# Sheet4.net
KiCad netlist of a schematic drawn in Altium Designer
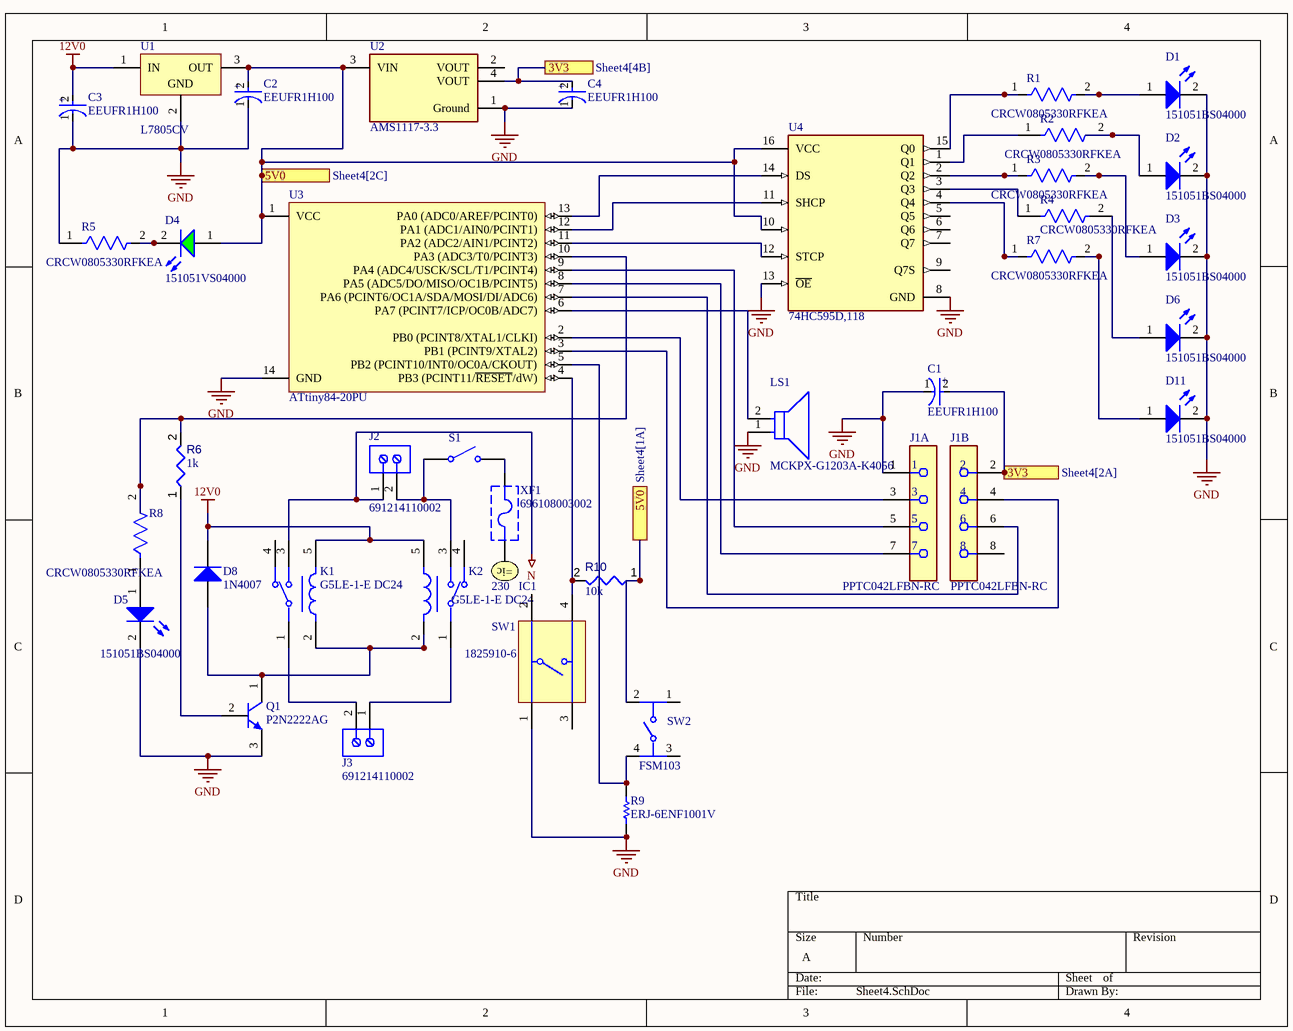
[diagram p0: Sheet4.SchDoc]

(export (version "E")
  (design (tool "Eeschema 10.0.6"))
  (components
    (comp (ref "C1")
      (value "EEUFR1H100")
      (footprint "FP-RAD-TH-D_5_0_5-L_11_1-MFG")
      (description "Aluminum Electrolytic Capacitors (Radial Lead Type) 10uF ±20% 50V")
      (fields (field (name "TOLERANCE") "20%") (field (name "VOLTAGE") "50V"))
      (libsource (lib "Altium Content Vault") (part "a00bbbee19879c290e62620ae7e47b1"))
    )
    (comp (ref "C2")
      (value "EEUFR1H100")
      (footprint "FP-RAD-TH-D_5_0_5-L_11_1-MFG")
      (description "Aluminum Electrolytic Capacitors (Radial Lead Type) 10uF ±20% 50V")
      (fields (field (name "TOLERANCE") "20%") (field (name "VOLTAGE") "50V"))
      (libsource (lib "Altium Content Vault") (part "a00bbbee19879c290e62620ae7e47b1"))
    )
    (comp (ref "C3")
      (value "EEUFR1H100")
      (footprint "FP-RAD-TH-D_5_0_5-L_11_1-MFG")
      (description "Aluminum Electrolytic Capacitors (Radial Lead Type) 10uF ±20% 50V")
      (fields (field (name "TOLERANCE") "20%") (field (name "VOLTAGE") "50V"))
      (libsource (lib "Altium Content Vault") (part "a00bbbee19879c290e62620ae7e47b1"))
    )
    (comp (ref "C4")
      (value "EEUFR1H100")
      (footprint "FP-RAD-TH-D_5_0_5-L_11_1-MFG")
      (description "Aluminum Electrolytic Capacitors (Radial Lead Type) 10uF ±20% 50V")
      (fields (field (name "TOLERANCE") "20%") (field (name "VOLTAGE") "50V"))
      (libsource (lib "Altium Content Vault") (part "a00bbbee19879c290e62620ae7e47b1"))
    )
    (comp (ref "D1")
      (value "151051BS04000")
      (footprint "WL-TMRC_D5.9H8.7")
      (libsource (lib "Altium Content Vault") (part "LED_Blue_1A-2K"))
    )
    (comp (ref "D2")
      (value "151051BS04000")
      (footprint "WL-TMRC_D5.9H8.7")
      (libsource (lib "Altium Content Vault") (part "LED_Blue_1A-2K"))
    )
    (comp (ref "D3")
      (value "151051BS04000")
      (footprint "WL-TMRC_D5.9H8.7")
      (libsource (lib "Altium Content Vault") (part "LED_Blue_1A-2K"))
    )
    (comp (ref "D4")
      (value "151051VS04000")
      (footprint "WL-TMRC_D5.9H8.7")
      (libsource (lib "Altium Content Vault") (part "LED_Green_1A-2K"))
    )
    (comp (ref "D5")
      (value "151051BS04000")
      (footprint "WL-TMRC_D5.9H8.7")
      (libsource (lib "Altium Content Vault") (part "LED_Blue_1A-2K"))
    )
    (comp (ref "D6")
      (value "151051BS04000")
      (footprint "WL-TMRC_D5.9H8.7")
      (libsource (lib "Altium Content Vault") (part "LED_Blue_1A-2K"))
    )
    (comp (ref "D8")
      (value "1N4007")
      (footprint "FAIR-DO-41-2")
      (description "General Purpose Rectifier, 1.1 V, 1.0 A, -55 to 175 degC, 2-Pin DO-41, RoHS, Tape and Reel")
      (fields (field (name "MANUFACTURER") "Fairchild"))
      (libsource (lib "Adheesha") (part "KESE-D_K1A2-2"))
    )
    (comp (ref "D11")
      (value "151051BS04000")
      (footprint "WL-TMRC_D5.9H8.7")
      (libsource (lib "Altium Content Vault") (part "LED_Blue_1A-2K"))
    )
    (comp (ref "IC1")
      (value "Initial Condition")
      (fields (field (name "INITIAL VOLTAGE") "230"))
      (libsource (lib "Simulation Generic Components") (part ".IC"))
    )
    (comp (ref "J1")
      (value "PPTC042LFBN-RC")
      (footprint "FP-PPTC042LFBN-RC-MFG")
      (description "CONN HDR 8POS 0.1 TIN PCB")
      (fields
        (field (name "OCTOPART") "https://octopart.com/pptc042lfbn-rc-sullins-271088")
        (field (name "MANUFACTURER") "Sullins")
      )
      (libsource (lib "") (part "f7953d7cc9e5fc6ef8e06ef09a26288_1"))
    )
    (comp (ref "J2")
      (value "691214110002")
      (footprint "691214110002")
      (fields (field (name "VOLTAGE") "300V"))
      (libsource (lib "Altium Content Vault") (part "TBL - 1R - 02P - Screw"))
    )
    (comp (ref "J3")
      (value "691214110002")
      (footprint "691214110002")
      (fields (field (name "VOLTAGE") "300V"))
      (libsource (lib "Altium Content Vault") (part "TBL - 1R - 02P - Screw"))
    )
    (comp (ref "K1")
      (value "G5LE-1-E DC24")
      (footprint "FP-G5LE-1-E_DC24-MFG")
      (description "RELAY GEN PURPOSE SPDT 16A 24V")
      (libsource (lib "Altium Content Vault") (part "c03b8d08e5d02e70a6880f365e34168"))
    )
    (comp (ref "K2")
      (value "G5LE-1-E DC24")
      (footprint "FP-G5LE-1-E_DC24-MFG")
      (description "RELAY GEN PURPOSE SPDT 16A 24V")
      (libsource (lib "") (part "c03b8d08e5d02e70a6880f365e34168_1"))
    )
    (comp (ref "LS1")
      (value "MCKPX-G1203A-K4056")
      (footprint "FP-MCKPX-G1203A-K4056-MFG")
      (description "MAGNETIC BUZZER AND TRANSDUCER - More Details")
      (fields
        (field (name "MANUFACTURER") "Multicomp Pro")
        (field (name "OCTOPART") "https://octopart.com/mckpx-g1203a-k4056-multicomp-12157154")
      )
      (libsource (lib "Altium Content Vault") (part "1973c4b650225fd2ddacaff6b763965"))
    )
    (comp (ref "Q1")
      (value "P2N2222AG")
      (footprint "ONSC-TO-92-3-29-11")
      (description "Amplifier Transistor, NPN Silicon, 3-Pin TO-92, Pb-Free, Bulk Box")
      (fields (field (name "MANUFACTURER") "On Semiconductor"))
      (libsource (lib "Altium Content Vault") (part "ONSC-NPN-C1B2E3-3"))
    )
    (comp (ref "R1")
      (value "CRCW0805330RFKEA")
      (footprint "FP-CRCW0805-e3-MFG")
      (description "RES Thick Film, 330Ω, 1%, 0.125W, 100ppm/°C, 0805")
      (fields (field (name "TOLERANCE") "1%"))
      (libsource (lib "Altium Content Vault") (part "1029c3af85768c4190bb7ad29bc67b5"))
    )
    (comp (ref "R2")
      (value "CRCW0805330RFKEA")
      (footprint "FP-CRCW0805-e3-MFG")
      (description "RES Thick Film, 330Ω, 1%, 0.125W, 100ppm/°C, 0805")
      (fields (field (name "TOLERANCE") "1%"))
      (libsource (lib "Altium Content Vault") (part "1029c3af85768c4190bb7ad29bc67b5"))
    )
    (comp (ref "R3")
      (value "CRCW0805330RFKEA")
      (footprint "FP-CRCW0805-e3-MFG")
      (description "RES Thick Film, 330Ω, 1%, 0.125W, 100ppm/°C, 0805")
      (fields (field (name "TOLERANCE") "1%"))
      (libsource (lib "Altium Content Vault") (part "1029c3af85768c4190bb7ad29bc67b5"))
    )
    (comp (ref "R4")
      (value "CRCW0805330RFKEA")
      (footprint "FP-CRCW0805-e3-MFG")
      (description "RES Thick Film, 330Ω, 1%, 0.125W, 100ppm/°C, 0805")
      (fields (field (name "TOLERANCE") "1%"))
      (libsource (lib "Altium Content Vault") (part "1029c3af85768c4190bb7ad29bc67b5"))
    )
    (comp (ref "R5")
      (value "CRCW0805330RFKEA")
      (footprint "FP-CRCW0805-e3-MFG")
      (description "RES Thick Film, 330Ω, 1%, 0.125W, 100ppm/°C, 0805")
      (fields (field (name "TOLERANCE") "1%"))
      (libsource (lib "Altium Content Vault") (part "1029c3af85768c4190bb7ad29bc67b5"))
    )
    (comp (ref "R6")
      (value "1k")
      (footprint "RESA60-630X240")
      (description "Axial Resistor, 47.5 KOhm, +/- 1%, 0.25 W, -55 to 155 degC, 2-Pin THD, RoHS, Bulk")
      (fields (field (name "MANUFACTURER") "Yageo") (field (name "TOLERANCE") "1%"))
      (libsource (lib "Adheesha") (part "RES-2"))
    )
    (comp (ref "R7")
      (value "CRCW0805330RFKEA")
      (footprint "FP-CRCW0805-e3-MFG")
      (description "RES Thick Film, 330Ω, 1%, 0.125W, 100ppm/°C, 0805")
      (fields (field (name "TOLERANCE") "1%"))
      (libsource (lib "Altium Content Vault") (part "1029c3af85768c4190bb7ad29bc67b5"))
    )
    (comp (ref "R8")
      (value "CRCW0805330RFKEA")
      (footprint "FP-CRCW0805-e3-MFG")
      (description "RES Thick Film, 330Ω, 1%, 0.125W, 100ppm/°C, 0805")
      (fields (field (name "TOLERANCE") "1%"))
      (libsource (lib "Altium Content Vault") (part "1029c3af85768c4190bb7ad29bc67b5"))
    )
    (comp (ref "R9")
      (value "ERJ-6ENF1001V")
      (footprint "RESC2013X70X40ML20T20")
      (description "Chip Resistor, 1 KOhm, +/- 1%, 0.125 W, -55 to 155 degC, 0805 (2012 Metric), RoHS, Tape and Reel")
      (fields (field (name "MANUFACTURER") "Panasonic"))
      (libsource (lib "Altium Content Vault") (part "RES-2"))
    )
    (comp (ref "R10")
      (value "10k")
      (footprint "RESA60-630X240")
      (description "Axial Resistor, 47.5 KOhm, +/- 1%, 0.25 W, -55 to 155 degC, 2-Pin THD, RoHS, Bulk")
      (fields (field (name "MANUFACTURER") "Yageo") (field (name "TOLERANCE") "1%"))
      (libsource (lib "Adheesha") (part "RES-2"))
    )
    (comp (ref "S1")
      (value "Single-Pole, Single-Throw Switch")
      (libsource (lib "Simulation Generic Components") (part "SPST SW"))
    )
    (comp (ref "SW1")
      (value "1825910-6")
      (footprint "TECO-1825910-6_V")
      (description "Tact Switch, SPST-NO, 0.05 A, -35 to 85 degC, 4-Pin THD, RoHS, Bulk")
      (fields (field (name "MANUFACTURER") "TE Connectivity"))
      (libsource (lib "Altium Content Vault") (part "SW-SPST-4_A"))
    )
    (comp (ref "SW2")
      (value "FSM103")
      (footprint "FP-FSM103-MFG")
      (description "SWITCH TACTILE SPST-NO 0.05A 24V")
      (libsource (lib "Altium Content Vault") (part "c0df99d12937e9d2da15afdedf14b17"))
    )
    (comp (ref "U1")
      (value "L7805CV")
      (footprint "TO220")
      (description "Positive Voltage Regulator, 5V, 3-Pin TO-220")
      (libsource (lib "Altium Content Vault") (part "PM-REG-L4940-SIL3"))
    )
    (comp (ref "U2")
      (value "AMS1117-3.3")
      (footprint "FP-AMS1117-IPC_C")
      (description "LDO Voltage Regulators 1A, 3.3V")
      (fields
        (field (name "OCTOPART") "https://octopart.com/ams1117-3.3-advanced+monolithic+systems-25899300")
        (field (name "MANUFACTURER") "Advanced Monolithic Systems")
      )
      (libsource (lib "Altium Content Vault") (part "8bdbb5f8e77002000e30dd2845d0354"))
    )
    (comp (ref "U3")
      (value "ATtiny84-20PU")
      (footprint "14P3")
      (libsource (lib "Altium Content Vault") (part "MC-8B-ATTINY24V-IL14"))
    )
    (comp (ref "U4")
      (value "74HC595D,118")
      (footprint "FP-SOT109-1-IPC_B")
      (description "IC SHIFT REGISTER 8BIT 16SOIC")
      (libsource (lib "Altium Content Vault") (part "7b153f231cfcc3ac06dee253bd56617"))
    )
    (comp (ref "XF1")
      (value "696108003002")
      (footprint "696108003002")
      (libsource (lib "Altium Content Vault") (part "Fuse Holder"))
    )
  )
  (nets
    (net (code "1") (name "/3V3") (class "Default")
      (node (ref "C1") (pin "2") (pinfunction "A_2") (pintype "passive"))
      (node (ref "C4") (pin "2") (pinfunction "A_2") (pintype "passive"))
      (node (ref "J1") (pin "2") (pinfunction "2_2") (pintype "passive"))
      (node (ref "U2") (pin "4") (pinfunction "VOUT_4") (pintype "passive"))
    )
    (net (code "2") (name "/5V0") (class "Default")
      (node (ref "C2") (pin "2") (pinfunction "A_2") (pintype "passive"))
      (node (ref "D4") (pin "1") (pinfunction "A_1") (pintype "passive"))
      (node (ref "R10") (pin "1") (pinfunction "1_1") (pintype "passive"))
      (node (ref "SW2") (pin "2") (pinfunction "2_2") (pintype "passive"))
      (node (ref "U1") (pin "3") (pinfunction "OUT_3") (pintype "power_in"))
      (node (ref "U2") (pin "3") (pinfunction "VIN_3") (pintype "power_in"))
      (node (ref "U3") (pin "1") (pinfunction "VCC_1") (pintype "power_in"))
      (node (ref "U4") (pin "10") (pinfunction "~{MR}_10") (pintype "input"))
      (node (ref "U4") (pin "16") (pinfunction "VCC_16") (pintype "power_in"))
    )
    (net (code "3") (name "12V0") (class "Default")
      (node (ref "C3") (pin "2") (pinfunction "A_2") (pintype "passive"))
      (node (ref "D8") (pin "1") (pinfunction "K_1") (pintype "passive"))
      (node (ref "K1") (pin "5") (pinfunction "5_5") (pintype "passive"))
      (node (ref "K2") (pin "5") (pinfunction "5_5") (pintype "passive"))
      (node (ref "U1") (pin "1") (pinfunction "IN_1") (pintype "power_in"))
    )
    (net (code "4") (name "GND") (class "Default")
      (node (ref "C1") (pin "1") (pinfunction "C_1") (pintype "passive"))
      (node (ref "C2") (pin "1") (pinfunction "C_1") (pintype "passive"))
      (node (ref "C3") (pin "1") (pinfunction "C_1") (pintype "passive"))
      (node (ref "C4") (pin "1") (pinfunction "C_1") (pintype "passive"))
      (node (ref "D1") (pin "2") (pinfunction "K_2") (pintype "passive"))
      (node (ref "D11") (pin "2") (pinfunction "K_2") (pintype "passive"))
      (node (ref "D2") (pin "2") (pinfunction "K_2") (pintype "passive"))
      (node (ref "D3") (pin "2") (pinfunction "K_2") (pintype "passive"))
      (node (ref "D5") (pin "2") (pinfunction "K_2") (pintype "passive"))
      (node (ref "D6") (pin "2") (pinfunction "K_2") (pintype "passive"))
      (node (ref "J1") (pin "1") (pinfunction "1_1") (pintype "passive"))
      (node (ref "LS1") (pin "1") (pinfunction "C_1") (pintype "passive"))
      (node (ref "Q1") (pin "3") (pinfunction "E_3") (pintype "passive"))
      (node (ref "R5") (pin "1") (pinfunction "1_1") (pintype "passive"))
      (node (ref "R9") (pin "1") (pinfunction "1_1") (pintype "passive"))
      (node (ref "SW1") (pin "1") (pinfunction "1_1") (pintype "passive"))
      (node (ref "U1") (pin "2") (pinfunction "GND_2") (pintype "power_in"))
      (node (ref "U2") (pin "1") (pinfunction "Ground_1") (pintype "power_in"))
      (node (ref "U3") (pin "14") (pinfunction "GND_14") (pintype "power_in"))
      (node (ref "U4") (pin "13") (pinfunction "~{OE}_13") (pintype "input"))
      (node (ref "U4") (pin "8") (pinfunction "GND_8") (pintype "power_in"))
    )
    (net (code "5") (name "N") (class "Default")
      (node (ref "J2") (pin "1") (pinfunction "1_1") (pintype "passive"))
      (node (ref "K1") (pin "3") (pinfunction "3_3") (pintype "passive"))
    )
    (net (code "6") (name "Net-(D1-A)") (class "Default")
      (node (ref "D1") (pin "1") (pinfunction "A_1") (pintype "passive"))
      (node (ref "R1") (pin "2") (pinfunction "2_2") (pintype "passive"))
    )
    (net (code "7") (name "Net-(D2-A)") (class "Default")
      (node (ref "D2") (pin "1") (pinfunction "A_1") (pintype "passive"))
      (node (ref "R2") (pin "2") (pinfunction "2_2") (pintype "passive"))
    )
    (net (code "8") (name "Net-(D3-A)") (class "Default")
      (node (ref "D3") (pin "1") (pinfunction "A_1") (pintype "passive"))
      (node (ref "R3") (pin "2") (pinfunction "2_2") (pintype "passive"))
    )
    (net (code "9") (name "Net-(D4-K)") (class "Default")
      (node (ref "D4") (pin "2") (pinfunction "K_2") (pintype "passive"))
      (node (ref "R5") (pin "2") (pinfunction "2_2") (pintype "passive"))
    )
    (net (code "10") (name "Net-(D5-A)") (class "Default")
      (node (ref "D5") (pin "1") (pinfunction "A_1") (pintype "passive"))
      (node (ref "R8") (pin "1") (pinfunction "1_1") (pintype "passive"))
    )
    (net (code "11") (name "Net-(D6-A)") (class "Default")
      (node (ref "D6") (pin "1") (pinfunction "A_1") (pintype "passive"))
      (node (ref "R4") (pin "2") (pinfunction "2_2") (pintype "passive"))
    )
    (net (code "12") (name "Net-(D8-A)") (class "Default")
      (node (ref "D8") (pin "2") (pinfunction "A_2") (pintype "passive"))
      (node (ref "K1") (pin "2") (pinfunction "2_2") (pintype "passive"))
      (node (ref "K2") (pin "2") (pinfunction "2_2") (pintype "passive"))
      (node (ref "Q1") (pin "1") (pinfunction "C_1") (pintype "passive"))
    )
    (net (code "13") (name "Net-(D11-A)") (class "Default")
      (node (ref "D11") (pin "1") (pinfunction "A_1") (pintype "passive"))
      (node (ref "R7") (pin "2") (pinfunction "2_2") (pintype "passive"))
    )
    (net (code "14") (name "Net-(IC1-Pad1)") (class "Default")
      (node (ref "IC1") (pin "1") (pinfunction "1_1") (pintype "passive"))
      (node (ref "XF1") (pin "1") (pinfunction "1_1") (pintype "passive"))
    )
    (net (code "15") (name "Net-(J2-Pad2)") (class "Default")
      (node (ref "J2") (pin "2") (pinfunction "2_2") (pintype "passive"))
      (node (ref "K2") (pin "3") (pinfunction "3_3") (pintype "passive"))
      (node (ref "S1") (pin "1") (pinfunction "1_1") (pintype "passive"))
    )
    (net (code "16") (name "Net-(J3-Pad1)") (class "Default")
      (node (ref "J3") (pin "1") (pinfunction "1_1") (pintype "passive"))
      (node (ref "K2") (pin "1") (pinfunction "1_1") (pintype "passive"))
    )
    (net (code "17") (name "Net-(J3-Pad2)") (class "Default")
      (node (ref "J3") (pin "2") (pinfunction "2_2") (pintype "passive"))
      (node (ref "K1") (pin "1") (pinfunction "1_1") (pintype "passive"))
    )
    (net (code "18") (name "Net-(LS1-A)") (class "Default")
      (node (ref "LS1") (pin "2") (pinfunction "A_2") (pintype "passive"))
      (node (ref "U3") (pin "6") (pinfunction "PA7_(PCINT7/ICP/OC0B/ADC7)_6") (pintype "bidirectional"))
    )
    (net (code "19") (name "Net-(Q1-B)") (class "Default")
      (node (ref "Q1") (pin "2") (pinfunction "B_2") (pintype "passive"))
      (node (ref "R6") (pin "1") (pinfunction "1_1") (pintype "passive"))
    )
    (net (code "20") (name "Net-(S1-Pad2)") (class "Default")
      (node (ref "S1") (pin "2") (pinfunction "2_2") (pintype "passive"))
      (node (ref "XF1") (pin "2") (pinfunction "2_2") (pintype "passive"))
    )
    (net (code "21") (name "Net-(U3-PA0_(ADC0{slash}AREF{slash}PCINT0))") (class "Default")
      (node (ref "U3") (pin "13") (pinfunction "PA0_(ADC0/AREF/PCINT0)_13") (pintype "bidirectional"))
      (node (ref "U4") (pin "14") (pinfunction "DS_14") (pintype "input"))
    )
    (net (code "22") (name "Net-(U3-PA1_(ADC1{slash}AIN0{slash}PCINT1))") (class "Default")
      (node (ref "U3") (pin "12") (pinfunction "PA1_(ADC1/AIN0/PCINT1)_12") (pintype "bidirectional"))
      (node (ref "U4") (pin "11") (pinfunction "SHCP_11") (pintype "input"))
    )
    (net (code "23") (name "Net-(U3-PA2_(ADC2{slash}AIN1{slash}PCINT2))") (class "Default")
      (node (ref "U3") (pin "11") (pinfunction "PA2_(ADC2/AIN1/PCINT2)_11") (pintype "bidirectional"))
      (node (ref "U4") (pin "12") (pinfunction "STCP_12") (pintype "input"))
    )
    (net (code "24") (name "Net-(U3-PA3_(ADC3{slash}T0{slash}PCINT3))") (class "Default")
      (node (ref "R6") (pin "2") (pinfunction "2_2") (pintype "passive"))
      (node (ref "R8") (pin "2") (pinfunction "2_2") (pintype "passive"))
      (node (ref "U3") (pin "10") (pinfunction "PA3_(ADC3/T0/PCINT3)_10") (pintype "bidirectional"))
    )
    (net (code "25") (name "Net-(U3-PA4_(ADC4{slash}USCK{slash}SCL{slash}T1{slash}PCINT4))") (class "Default")
      (node (ref "J1") (pin "5") (pinfunction "5_5") (pintype "passive"))
      (node (ref "U3") (pin "9") (pinfunction "PA4_(ADC4/USCK/SCL/T1/PCINT4)_9") (pintype "bidirectional"))
    )
    (net (code "26") (name "Net-(U3-PA5_(ADC5{slash}DO{slash}MISO{slash}OC1B{slash}PCINT5))") (class "Default")
      (node (ref "J1") (pin "7") (pinfunction "7_7") (pintype "passive"))
      (node (ref "U3") (pin "8") (pinfunction "PA5_(ADC5/DO/MISO/OC1B/PCINT5)_8") (pintype "bidirectional"))
    )
    (net (code "27") (name "Net-(U3-PA6_(PCINT6{slash}OC1A{slash}SDA{slash}MOSI{slash}DI{slash}ADC6))") (class "Default")
      (node (ref "J1") (pin "6") (pinfunction "6_6") (pintype "passive"))
      (node (ref "U3") (pin "7") (pinfunction "PA6_(PCINT6/OC1A/SDA/MOSI/DI/ADC6)_7") (pintype "bidirectional"))
    )
    (net (code "28") (name "Net-(U3-PB0_(PCINT8{slash}XTAL1{slash}CLKI))") (class "Default")
      (node (ref "J1") (pin "3") (pinfunction "3_3") (pintype "passive"))
      (node (ref "U3") (pin "2") (pinfunction "PB0_(PCINT8/XTAL1/CLKI)_2") (pintype "bidirectional"))
    )
    (net (code "29") (name "Net-(U3-PB1_(PCINT9{slash}XTAL2))") (class "Default")
      (node (ref "J1") (pin "4") (pinfunction "4_4") (pintype "passive"))
      (node (ref "U3") (pin "3") (pinfunction "PB1_(PCINT9/XTAL2)_3") (pintype "bidirectional"))
    )
    (net (code "30") (name "Net-(U3-PB2_(PCINT10{slash}INT0{slash}OC0A{slash}CKOUT))") (class "Default")
      (node (ref "R9") (pin "2") (pinfunction "2_2") (pintype "passive"))
      (node (ref "SW2") (pin "4") (pinfunction "4_4") (pintype "passive"))
      (node (ref "U3") (pin "5") (pinfunction "PB2_(PCINT10/INT0/OC0A/CKOUT)_5") (pintype "bidirectional"))
    )
    (net (code "31") (name "Net-(U3-PB3_(PCINT11{slash}~{RESET}{slash}dW))") (class "Default")
      (node (ref "R10") (pin "2") (pinfunction "2_2") (pintype "passive"))
      (node (ref "SW1") (pin "4") (pinfunction "4_4") (pintype "passive"))
      (node (ref "U3") (pin "4") (pinfunction "PB3_(PCINT11/~{RESET}/dW)_4") (pintype "bidirectional"))
    )
    (net (code "32") (name "Net-(U4-Q0)") (class "Default")
      (node (ref "R1") (pin "1") (pinfunction "1_1") (pintype "passive"))
      (node (ref "U4") (pin "15") (pinfunction "Q0_15") (pintype "output"))
    )
    (net (code "33") (name "Net-(U4-Q1)") (class "Default")
      (node (ref "R2") (pin "1") (pinfunction "1_1") (pintype "passive"))
      (node (ref "U4") (pin "1") (pinfunction "Q1_1") (pintype "output"))
    )
    (net (code "34") (name "Net-(U4-Q2)") (class "Default")
      (node (ref "R3") (pin "1") (pinfunction "1_1") (pintype "passive"))
      (node (ref "U4") (pin "2") (pinfunction "Q2_2") (pintype "output"))
    )
    (net (code "35") (name "Net-(U4-Q3)") (class "Default")
      (node (ref "R4") (pin "1") (pinfunction "1_1") (pintype "passive"))
      (node (ref "U4") (pin "3") (pinfunction "Q3_3") (pintype "output"))
    )
    (net (code "36") (name "Net-(U4-Q4)") (class "Default")
      (node (ref "R7") (pin "1") (pinfunction "1_1") (pintype "passive"))
      (node (ref "U4") (pin "4") (pinfunction "Q4_4") (pintype "output"))
    )
    (net (code "37") (name "unconnected-(J1-Pad8)") (class "Default")
      (node (ref "J1") (pin "8") (pinfunction "8_8") (pintype "passive"))
    )
    (net (code "38") (name "unconnected-(K1-Pad4)") (class "Default")
      (node (ref "K1") (pin "4") (pinfunction "4_4") (pintype "passive"))
    )
    (net (code "39") (name "unconnected-(K2-Pad4)") (class "Default")
      (node (ref "K2") (pin "4") (pinfunction "4_4") (pintype "passive"))
    )
    (net (code "40") (name "unconnected-(SW1-Pad2)") (class "Default")
      (node (ref "SW1") (pin "2") (pinfunction "2_2") (pintype "passive"))
    )
    (net (code "41") (name "unconnected-(SW1-Pad3)") (class "Default")
      (node (ref "SW1") (pin "3") (pinfunction "3_3") (pintype "passive"))
    )
    (net (code "42") (name "unconnected-(SW2-Pad1)") (class "Default")
      (node (ref "SW2") (pin "1") (pinfunction "1_1") (pintype "passive"))
    )
    (net (code "43") (name "unconnected-(SW2-Pad3)") (class "Default")
      (node (ref "SW2") (pin "3") (pinfunction "3_3") (pintype "passive"))
    )
    (net (code "44") (name "unconnected-(U2-VOUT-Pad2)") (class "Default")
      (node (ref "U2") (pin "2") (pinfunction "VOUT_2") (pintype "passive"))
    )
    (net (code "45") (name "unconnected-(U4-Q5-Pad5)") (class "Default")
      (node (ref "U4") (pin "5") (pinfunction "Q5_5") (pintype "output"))
    )
    (net (code "46") (name "unconnected-(U4-Q6-Pad6)") (class "Default")
      (node (ref "U4") (pin "6") (pinfunction "Q6_6") (pintype "output"))
    )
    (net (code "47") (name "unconnected-(U4-Q7-Pad7)") (class "Default")
      (node (ref "U4") (pin "7") (pinfunction "Q7_7") (pintype "output"))
    )
    (net (code "48") (name "unconnected-(U4-Q7S-Pad9)") (class "Default")
      (node (ref "U4") (pin "9") (pinfunction "Q7S_9") (pintype "output"))
    )
  )
)
